# STM32-2.net
KiCad netlist of a schematic drawn in Altium Designer
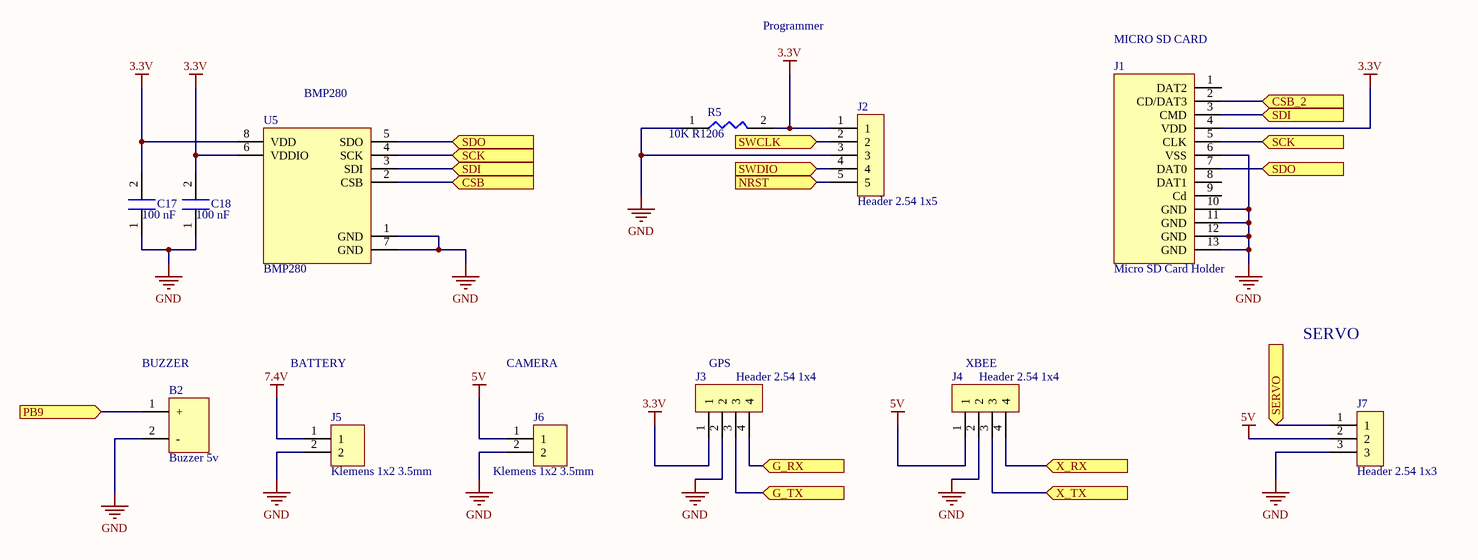
[diagram p0: STM32-2.SchDoc]

(export (version "E")
  (design (tool "Eeschema 10.0.6"))
  (components
    (comp (ref "B2") (value "Buzzer 5v") (footprint "Buzzer 5v") (libsource (lib "Stm32") (part "Buzzer 5v")))
    (comp (ref "C17") (value "100 nF") (footprint "C1206") (libsource (lib "Stm32") (part "100 nF")))
    (comp (ref "C18") (value "100 nF") (footprint "C1206") (libsource (lib "Stm32") (part "100 nF")))
    (comp (ref "J1")
      (value "Micro SD Card Holder")
      (footprint "Micro SD Card Holder")
      (libsource (lib "Stm32") (part "Micro SD Card Holder"))
    )
    (comp (ref "J2")
      (value "Header 2.54 1x5")
      (footprint "Header 2.54 1x5")
      (libsource (lib "Stm32") (part "Header 2.54 1x5"))
    )
    (comp (ref "J3")
      (value "Header 2.54 1x4")
      (footprint "Header 2.54 1x4")
      (libsource (lib "Stm32") (part "Header 2.54 1x4"))
    )
    (comp (ref "J4")
      (value "Header 2.54 1x4")
      (footprint "Header 2.54 1x4")
      (libsource (lib "Stm32") (part "Header 2.54 1x4"))
    )
    (comp (ref "J5")
      (value "Klemens 1x2 3.5mm")
      (footprint "Klemens 1x2 - 3.5mm")
      (libsource (lib "Stm32") (part "Klemens 1x2 3.5mm"))
    )
    (comp (ref "J6")
      (value "Klemens 1x2 3.5mm")
      (footprint "Klemens 1x2 - 3.5mm")
      (libsource (lib "Stm32") (part "Klemens 1x2 3.5mm"))
    )
    (comp (ref "J7")
      (value "Header 2.54 1x3")
      (footprint "Header 2.54 1x3")
      (libsource (lib "Stm32") (part "Header 2.54 1x3"))
    )
    (comp (ref "R5")
      (value "10K R1206")
      (footprint "R1206 Resıstor")
      (libsource (lib "Stm32") (part "10K R1206"))
    )
    (comp (ref "U5")
      (value "BMP280")
      (footprint "BMP280")
      (description "BMP280 SENSOR")
      (libsource (lib "Stm32") (part "BMP280"))
    )
  )
  (nets
    (net (code "1") (name "/CSB") (class "Default")
      (node (ref "U5") (pin "2") (pinfunction "CSB_2") (pintype "passive"))
    )
    (net (code "2") (name "/CSB_2") (class "Default")
      (node (ref "J1") (pin "2") (pinfunction "CD/DAT3_2") (pintype "passive"))
    )
    (net (code "3") (name "/G_RX") (class "Default")
      (node (ref "J3") (pin "4") (pinfunction "4_4") (pintype "passive"))
    )
    (net (code "4") (name "/G_TX") (class "Default")
      (node (ref "J3") (pin "3") (pinfunction "3_3") (pintype "passive"))
    )
    (net (code "5") (name "/NRST") (class "Default")
      (node (ref "J2") (pin "5") (pinfunction "5_5") (pintype "passive"))
    )
    (net (code "6") (name "/PB9") (class "Default")
      (node (ref "B2") (pin "1") (pinfunction "+_1") (pintype "passive"))
    )
    (net (code "7") (name "/SCK") (class "Default")
      (node (ref "J1") (pin "5") (pinfunction "CLK_5") (pintype "passive"))
      (node (ref "U5") (pin "4") (pinfunction "SCK_4") (pintype "passive"))
    )
    (net (code "8") (name "/SDI") (class "Default")
      (node (ref "J1") (pin "3") (pinfunction "CMD_3") (pintype "passive"))
      (node (ref "U5") (pin "3") (pinfunction "SDI_3") (pintype "passive"))
    )
    (net (code "9") (name "/SDO") (class "Default")
      (node (ref "J1") (pin "7") (pinfunction "DAT0_7") (pintype "passive"))
      (node (ref "U5") (pin "5") (pinfunction "SDO_5") (pintype "passive"))
    )
    (net (code "10") (name "/SERVO") (class "Default")
      (node (ref "J7") (pin "1") (pinfunction "1_1") (pintype "passive"))
    )
    (net (code "11") (name "/SWCLK") (class "Default")
      (node (ref "J2") (pin "2") (pinfunction "2_2") (pintype "passive"))
    )
    (net (code "12") (name "/SWDIO") (class "Default")
      (node (ref "J2") (pin "4") (pinfunction "4_4") (pintype "passive"))
    )
    (net (code "13") (name "/X_RX") (class "Default")
      (node (ref "J4") (pin "4") (pinfunction "4_4") (pintype "passive"))
    )
    (net (code "14") (name "/X_TX") (class "Default")
      (node (ref "J4") (pin "3") (pinfunction "3_3") (pintype "passive"))
    )
    (net (code "15") (name "3.3V") (class "Default")
      (node (ref "C17") (pin "2") (pinfunction "2_2") (pintype "passive"))
      (node (ref "C18") (pin "2") (pinfunction "2_2") (pintype "passive"))
      (node (ref "J1") (pin "4") (pinfunction "VDD_4") (pintype "passive"))
      (node (ref "J2") (pin "1") (pinfunction "1_1") (pintype "passive"))
      (node (ref "J3") (pin "1") (pinfunction "1_1") (pintype "passive"))
      (node (ref "R5") (pin "2") (pinfunction "2_2") (pintype "passive"))
      (node (ref "U5") (pin "6") (pinfunction "VDDIO_6") (pintype "passive"))
      (node (ref "U5") (pin "8") (pinfunction "VDD_8") (pintype "passive"))
    )
    (net (code "16") (name "5V") (class "Default")
      (node (ref "J4") (pin "1") (pinfunction "1_1") (pintype "passive"))
      (node (ref "J6") (pin "1") (pinfunction "1_1") (pintype "passive"))
      (node (ref "J7") (pin "2") (pinfunction "2_2") (pintype "passive"))
    )
    (net (code "17") (name "7.4V") (class "Default")
      (node (ref "J5") (pin "1") (pinfunction "1_1") (pintype "passive"))
    )
    (net (code "18") (name "GND") (class "Default")
      (node (ref "B2") (pin "2") (pinfunction "-_2") (pintype "passive"))
      (node (ref "C17") (pin "1") (pinfunction "1_1") (pintype "passive"))
      (node (ref "C18") (pin "1") (pinfunction "1_1") (pintype "passive"))
      (node (ref "J1") (pin "10") (pinfunction "GND_10") (pintype "passive"))
      (node (ref "J1") (pin "11") (pinfunction "GND_11") (pintype "passive"))
      (node (ref "J1") (pin "12") (pinfunction "GND_12") (pintype "passive"))
      (node (ref "J1") (pin "13") (pinfunction "GND_13") (pintype "passive"))
      (node (ref "J1") (pin "6") (pinfunction "VSS_6") (pintype "passive"))
      (node (ref "J2") (pin "3") (pinfunction "3_3") (pintype "passive"))
      (node (ref "J3") (pin "2") (pinfunction "2_2") (pintype "passive"))
      (node (ref "J4") (pin "2") (pinfunction "2_2") (pintype "passive"))
      (node (ref "J5") (pin "2") (pinfunction "2_2") (pintype "passive"))
      (node (ref "J6") (pin "2") (pinfunction "2_2") (pintype "passive"))
      (node (ref "J7") (pin "3") (pinfunction "3_3") (pintype "passive"))
      (node (ref "R5") (pin "1") (pinfunction "1_1") (pintype "passive"))
      (node (ref "U5") (pin "1") (pinfunction "GND_1") (pintype "passive"))
      (node (ref "U5") (pin "7") (pinfunction "GND_7") (pintype "passive"))
    )
    (net (code "19") (name "unconnected-(J1-Cd-Pad9)") (class "Default")
      (node (ref "J1") (pin "9") (pinfunction "Cd_9") (pintype "passive"))
    )
    (net (code "20") (name "unconnected-(J1-DAT1-Pad8)") (class "Default")
      (node (ref "J1") (pin "8") (pinfunction "DAT1_8") (pintype "passive"))
    )
    (net (code "21") (name "unconnected-(J1-DAT2-Pad1)") (class "Default")
      (node (ref "J1") (pin "1") (pinfunction "DAT2_1") (pintype "passive"))
    )
  )
)
